# MainBoard_V100_PER.net
KiCad netlist of a schematic drawn in Altium Designer
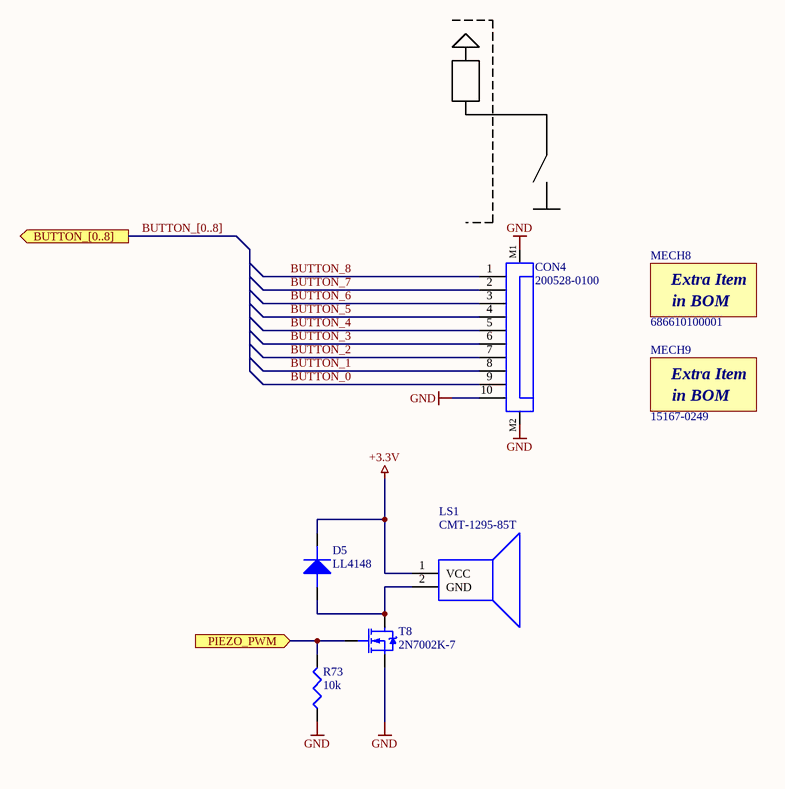
[diagram p0: MainBoard_V100_PER.SchDoc]

(export (version "E")
  (design (tool "Eeschema 10.0.6"))
  (components
    (comp (ref "CON4")
      (value "200528-0100")
      (footprint "CON_FPC10_1MM_MOLEX_200528-0100")
      (description "FFC / FPC Board Connector, 1 mm, 10 Contacts, Receptacle, Easy-On, Surface Mount")
      (fields (field (name "PART NUMBER") "CON_FPC_MOLEX_200528-0100"))
      (libsource (lib "ALTIUM_DB_LIB") (part "FPC_10PIN"))
    )
    (comp (ref "D5")
      (value "LL4148")
      (footprint "SOD80")
      (description "General Purpose, Power, Switching Small Signal Diode, SOD-80, 100V, 0.15A, 175C")
      (libsource (lib "ALTIUM_DB_LIB") (part "DIODE"))
    )
    (comp (ref "LS1")
      (value "CMT-1295-85T")
      (footprint "BUZZER_KXG1205")
      (description "Piezo Buzzers & Audio Indicators, 2.4kHz, 12mm, Magnetic, 3V THT")
      (libsource (lib "ALTIUM_DB_LIB") (part "BUZZER"))
    )
    (comp (ref "MECH8")
      (value "686610100001")
      (description "FFC / FPC Jumper Cables WR-FFC 1mm Type 1 10P 100mm length")
      (libsource (lib "ALTIUM_DB_LIB") (part "Extra Part"))
    )
    (comp (ref "MECH9")
      (value "15167-0249")
      (description "FFC / FPC Jumper Cables FFC 1.00mm Type A 10 contact 76mm")
      (libsource (lib "ALTIUM_DB_LIB") (part "Extra Part"))
    )
    (comp (ref "R73")
      (value "10k")
      (footprint "0805")
      (description "10k 0805 0.125W 1%")
      (fields (field (name "PART NUMBER") "SMD0805-10k 1%"))
      (libsource (lib "ALTIUM_DB_LIB") (part "RESISTOR"))
    )
    (comp (ref "T8")
      (value "2N7002K-7")
      (footprint "SOT-23")
      (description "2N7002K-7 Power MOSFET, N Channel, 60 V, 300 mA, 2 ohm, SOT-23, Surface Mount")
      (libsource (lib "ALTIUM_DB_LIB") (part "MOSFET_N_CH"))
    )
  )
  (nets
    (net (code "1") (name "+3.3V") (class "Default")
      (node (ref "D5") (pin "K") (pinfunction "K_K") (pintype "passive"))
      (node (ref "LS1") (pin "1") (pinfunction "VCC_1") (pintype "passive"))
    )
    (net (code "2") (name "/BUTTON_0") (class "Default")
      (node (ref "CON4") (pin "9") (pinfunction "9_9") (pintype "passive"))
    )
    (net (code "3") (name "/BUTTON_1") (class "Default")
      (node (ref "CON4") (pin "8") (pinfunction "8_8") (pintype "passive"))
    )
    (net (code "4") (name "/BUTTON_2") (class "Default")
      (node (ref "CON4") (pin "7") (pinfunction "7_7") (pintype "passive"))
    )
    (net (code "5") (name "/BUTTON_3") (class "Default")
      (node (ref "CON4") (pin "6") (pinfunction "6_6") (pintype "passive"))
    )
    (net (code "6") (name "/BUTTON_4") (class "Default")
      (node (ref "CON4") (pin "5") (pinfunction "5_5") (pintype "passive"))
    )
    (net (code "7") (name "/BUTTON_5") (class "Default")
      (node (ref "CON4") (pin "4") (pinfunction "4_4") (pintype "passive"))
    )
    (net (code "8") (name "/BUTTON_6") (class "Default")
      (node (ref "CON4") (pin "3") (pinfunction "3_3") (pintype "passive"))
    )
    (net (code "9") (name "/BUTTON_7") (class "Default")
      (node (ref "CON4") (pin "2") (pinfunction "2_2") (pintype "passive"))
    )
    (net (code "10") (name "/BUTTON_8") (class "Default")
      (node (ref "CON4") (pin "1") (pinfunction "1_1") (pintype "passive"))
    )
    (net (code "12") (name "/PIEZO_PWM") (class "Default")
      (node (ref "R73") (pin "2") (pintype "passive"))
      (node (ref "T8") (pin "1") (pinfunction "G_1") (pintype "passive"))
    )
    (net (code "13") (name "GND") (class "Default")
      (node (ref "CON4") (pin "10") (pinfunction "10_10") (pintype "passive"))
      (node (ref "CON4") (pin "M1") (pinfunction "M1_M1") (pintype "passive"))
      (node (ref "CON4") (pin "M2") (pinfunction "M2_M2") (pintype "passive"))
      (node (ref "R73") (pin "1") (pintype "passive"))
      (node (ref "T8") (pin "2") (pinfunction "S_2") (pintype "passive"))
    )
    (net (code "14") (name "Net-(LS1-GND)") (class "Default")
      (node (ref "D5") (pin "A") (pinfunction "A_A") (pintype "passive"))
      (node (ref "LS1") (pin "2") (pinfunction "GND_2") (pintype "passive"))
      (node (ref "T8") (pin "3") (pinfunction "D_3") (pintype "passive"))
    )
  )
)
